# esquema001.net
KiCad netlist of a schematic drawn in EAGLE
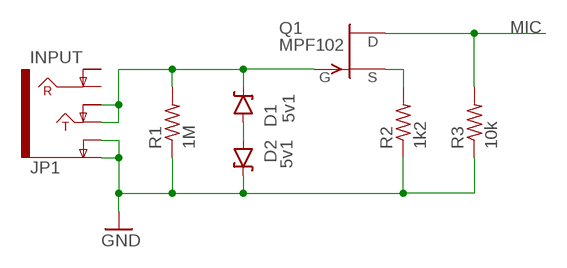
[diagram p0: schematic, sheet 1]
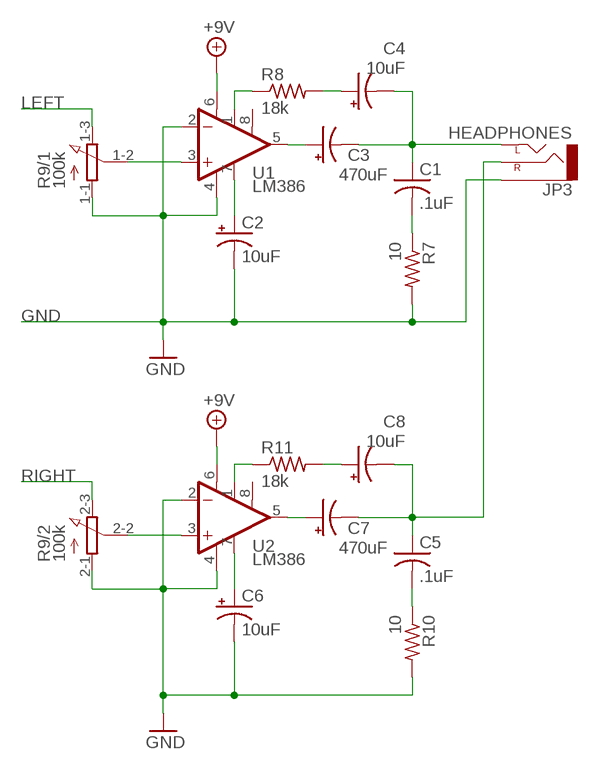
[diagram p1: schematic, sheet 2]
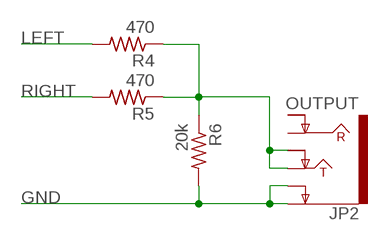
[diagram p2: schematic, sheet 3]
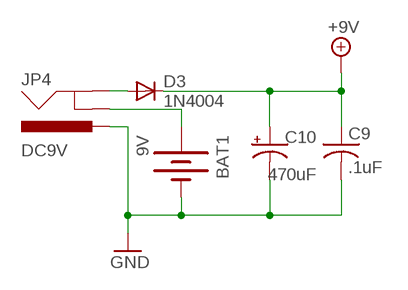
[diagram p3: schematic, sheet 4]

(export (version "E")
  (design (tool "Eeschema 10.0.6"))
  (components
    (comp (ref "BAT1")
      (value "9V")
      (footprint "eagle-import:BATTCON_9V")
      (libsource (lib "eagle-import") (part "BATTERY9V"))
    )
    (comp (ref "C9")
      (value ".1uF")
      (footprint "eagle-import:C050-024X044")
      (libsource (lib "eagle-import") (part "C-US050-024X044"))
    )
    (comp (ref "C10")
      (value "470uF")
      (footprint "eagle-import:E2,5-7")
      (libsource (lib "eagle-import") (part "CPOL-USE2.5-7"))
    )
    (comp (ref "D3")
      (value "1N4004")
      (footprint "eagle-import:DO41-10")
      (libsource (lib "eagle-import") (part "1N4004"))
    )
    (comp (ref "JP4")
      (value "DC9V")
      (footprint "eagle-import:POWER_JACK_PTH")
      (libsource (lib "eagle-import") (part "POWER_JACKPTH"))
    )
    (comp (ref "D1")
      (value "5v1")
      (footprint "eagle-import:DIODE-ZENER")
      (libsource (lib "eagle-import") (part "DIODE-ZENERPTH"))
    )
    (comp (ref "D2")
      (value "5v1")
      (footprint "eagle-import:DIODE-ZENER")
      (libsource (lib "eagle-import") (part "DIODE-ZENERPTH"))
    )
    (comp (ref "JP1")
      (value "INPUT")
      (footprint "eagle-import:AUDIO-JACK-.25-INCH-HORIZ-PTH")
      (libsource (lib "eagle-import") (part "AUDIO-JACK4-.25-HORIZ-TRS"))
    )
    (comp (ref "Q1")
      (value "MPF102")
      (footprint "eagle-import:TO92-")
      (libsource (lib "eagle-import") (part "?5482N4"))
    )
    (comp (ref "R1")
      (value "1M")
      (footprint "eagle-import:0204_7")
      (libsource (lib "eagle-import") (part "R-US_0204/7"))
    )
    (comp (ref "R2")
      (value "1k2")
      (footprint "eagle-import:0204_7")
      (libsource (lib "eagle-import") (part "R-US_0204/7"))
    )
    (comp (ref "R3")
      (value "10k")
      (footprint "eagle-import:0204_7")
      (libsource (lib "eagle-import") (part "R-US_0204/7"))
    )
    (comp (ref "JP2")
      (value "OUTPUT")
      (footprint "eagle-import:AUDIO-JACK-.25-INCH-HORIZ-PTH")
      (libsource (lib "eagle-import") (part "AUDIO-JACK4-.25-HORIZ-TRS"))
    )
    (comp (ref "R4")
      (value "470")
      (footprint "eagle-import:0204_7")
      (libsource (lib "eagle-import") (part "R-US_0204/7"))
    )
    (comp (ref "R5")
      (value "470")
      (footprint "eagle-import:0204_7")
      (libsource (lib "eagle-import") (part "R-US_0204/7"))
    )
    (comp (ref "R6")
      (value "20k")
      (footprint "eagle-import:0204_7")
      (libsource (lib "eagle-import") (part "R-US_0204/7"))
    )
    (comp (ref "C1")
      (value ".1uF")
      (footprint "eagle-import:C050-024X044")
      (libsource (lib "eagle-import") (part "C-US050-024X044"))
    )
    (comp (ref "C2")
      (value "10uF")
      (footprint "eagle-import:E2,5-7")
      (libsource (lib "eagle-import") (part "CPOL-USE2.5-7"))
    )
    (comp (ref "C3")
      (value "470uF")
      (footprint "eagle-import:E2,5-7")
      (libsource (lib "eagle-import") (part "CPOL-USE2.5-7"))
    )
    (comp (ref "C4")
      (value "10uF")
      (footprint "eagle-import:E2,5-7")
      (libsource (lib "eagle-import") (part "CPOL-USE2.5-7"))
    )
    (comp (ref "C5")
      (value ".1uF")
      (footprint "eagle-import:C050-024X044")
      (libsource (lib "eagle-import") (part "C-US050-024X044"))
    )
    (comp (ref "C6")
      (value "10uF")
      (footprint "eagle-import:E2,5-7")
      (libsource (lib "eagle-import") (part "CPOL-USE2.5-7"))
    )
    (comp (ref "C7")
      (value "470uF")
      (footprint "eagle-import:E2,5-7")
      (libsource (lib "eagle-import") (part "CPOL-USE2.5-7"))
    )
    (comp (ref "C8")
      (value "10uF")
      (footprint "eagle-import:E2,5-7")
      (libsource (lib "eagle-import") (part "CPOL-USE2.5-7"))
    )
    (comp (ref "JP3")
      (value "HEADPHONES")
      (footprint "eagle-import:AUDIO-JACK")
      (libsource (lib "eagle-import") (part "AUDIO-JACKPTH"))
    )
    (comp (ref "R7")
      (value "10")
      (footprint "eagle-import:0204_7")
      (libsource (lib "eagle-import") (part "R-US_0204/7"))
    )
    (comp (ref "R8")
      (value "18k")
      (footprint "eagle-import:0204_7")
      (libsource (lib "eagle-import") (part "R-US_0204/7"))
    )
    (comp (ref "R9")
      (value "100k")
      (footprint "eagle-import:3RP_1610G")
      (libsource (lib "eagle-import") (part "3RP/1610G"))
    )
    (comp (ref "R10")
      (value "10")
      (footprint "eagle-import:0204_7")
      (libsource (lib "eagle-import") (part "R-US_0204/7"))
    )
    (comp (ref "R11")
      (value "18k")
      (footprint "eagle-import:0204_7")
      (libsource (lib "eagle-import") (part "R-US_0204/7"))
    )
    (comp (ref "U1")
      (value "LM386")
      (footprint "eagle-import:DIP08")
      (libsource (lib "eagle-import") (part "LM386"))
    )
    (comp (ref "U2")
      (value "LM386")
      (footprint "eagle-import:DIP08")
      (libsource (lib "eagle-import") (part "LM386"))
    )
  )
  (nets
    (net (code "1") (name "+9V") (class "Default")
      (node (ref "C10") (pin "+") (pinfunction "+_+") (pintype "passive"))
      (node (ref "C9") (pin "1") (pinfunction "1_1") (pintype "passive"))
      (node (ref "D3") (pin "C") (pinfunction "C_C") (pintype "passive"))
      (node (ref "U1") (pin "6") (pinfunction "V+_6") (pintype "power_in"))
      (node (ref "U2") (pin "6") (pinfunction "V+_6") (pintype "power_in"))
    )
    (net (code "2") (name "GND") (class "Default")
      (node (ref "BAT1") (pin "-") (pinfunction "-_-") (pintype "power_in"))
      (node (ref "C10") (pin "-") (pinfunction "-_-") (pintype "passive"))
      (node (ref "C2") (pin "-") (pinfunction "-_-") (pintype "passive"))
      (node (ref "C6") (pin "-") (pinfunction "-_-") (pintype "passive"))
      (node (ref "C9") (pin "2") (pinfunction "2_2") (pintype "passive"))
      (node (ref "D2") (pin "P$1") (pinfunction "C_P$1") (pintype "passive"))
      (node (ref "JP1") (pin "SLEEVE") (pinfunction "EARTH_SLEEVE") (pintype "bidirectional"))
      (node (ref "JP1") (pin "SLEEVE-NORM") (pinfunction "EARTH-NORM_SLEEVE-NORM") (pintype "bidirectional"))
      (node (ref "JP2") (pin "SLEEVE") (pinfunction "EARTH_SLEEVE") (pintype "bidirectional"))
      (node (ref "JP2") (pin "SLEEVE-NORM") (pinfunction "EARTH-NORM_SLEEVE-NORM") (pintype "bidirectional"))
      (node (ref "JP3") (pin "SLEEVE") (pinfunction "SLEEVE_SLEEVE") (pintype "bidirectional"))
      (node (ref "JP4") (pin "PWR") (pinfunction "PWR_PWR") (pintype "bidirectional"))
      (node (ref "R1") (pin "1") (pinfunction "1_1") (pintype "passive"))
      (node (ref "R10") (pin "2") (pinfunction "2_2") (pintype "passive"))
      (node (ref "R2") (pin "1") (pinfunction "1_1") (pintype "passive"))
      (node (ref "R3") (pin "1") (pinfunction "1_1") (pintype "passive"))
      (node (ref "R6") (pin "2") (pinfunction "2_2") (pintype "passive"))
      (node (ref "R7") (pin "2") (pinfunction "2_2") (pintype "passive"))
      (node (ref "R9") (pin "1-1") (pinfunction "A_1-1") (pintype "passive"))
      (node (ref "R9") (pin "2-1") (pinfunction "A_2-1") (pintype "passive"))
      (node (ref "U1") (pin "2") (pinfunction "-IN_2") (pintype "input"))
      (node (ref "U1") (pin "4") (pinfunction "V-_4") (pintype "power_in"))
      (node (ref "U2") (pin "2") (pinfunction "-IN_2") (pintype "input"))
      (node (ref "U2") (pin "4") (pinfunction "V-_4") (pintype "power_in"))
    )
    (net (code "3") (name "LEFT") (class "Default")
      (node (ref "R4") (pin "2") (pinfunction "2_2") (pintype "passive"))
      (node (ref "R9") (pin "1-3") (pinfunction "E_1-3") (pintype "passive"))
    )
    (net (code "4") (name "MIC") (class "Default")
      (node (ref "Q1") (pin "3") (pinfunction "D_3") (pintype "passive"))
      (node (ref "R3") (pin "2") (pinfunction "2_2") (pintype "passive"))
    )
    (net (code "5") (name "Net-(BAT1-Pad+)") (class "Default")
      (node (ref "BAT1") (pin "+") (pinfunction "+_+") (pintype "power_in"))
      (node (ref "JP4") (pin "GNDBREAK") (pinfunction "GNDBREAK_GNDBREAK") (pintype "bidirectional"))
    )
    (net (code "6") (name "Net-(C1-Pad2)") (class "Default")
      (node (ref "C1") (pin "2") (pinfunction "2_2") (pintype "passive"))
      (node (ref "R7") (pin "1") (pinfunction "1_1") (pintype "passive"))
    )
    (net (code "7") (name "Net-(C4-Pad+)") (class "Default")
      (node (ref "C4") (pin "+") (pinfunction "+_+") (pintype "passive"))
      (node (ref "R8") (pin "2") (pinfunction "2_2") (pintype "passive"))
    )
    (net (code "8") (name "Net-(C5-Pad2)") (class "Default")
      (node (ref "C5") (pin "2") (pinfunction "2_2") (pintype "passive"))
      (node (ref "R10") (pin "1") (pinfunction "1_1") (pintype "passive"))
    )
    (net (code "9") (name "Net-(C8-Pad+)") (class "Default")
      (node (ref "C8") (pin "+") (pinfunction "+_+") (pintype "passive"))
      (node (ref "R11") (pin "2") (pinfunction "2_2") (pintype "passive"))
    )
    (net (code "10") (name "Net-(D1-A)") (class "Default")
      (node (ref "D1") (pin "P$2") (pinfunction "A_P$2") (pintype "passive"))
      (node (ref "D2") (pin "P$2") (pinfunction "A_P$2") (pintype "passive"))
    )
    (net (code "11") (name "Net-(D1-C)") (class "Default")
      (node (ref "D1") (pin "P$1") (pinfunction "C_P$1") (pintype "passive"))
      (node (ref "JP1") (pin "TIP") (pinfunction "TIP_TIP") (pintype "bidirectional"))
      (node (ref "JP1") (pin "TIP-NORM") (pinfunction "TIP-NORM_TIP-NORM") (pintype "bidirectional"))
      (node (ref "Q1") (pin "1") (pinfunction "G_1") (pintype "passive"))
      (node (ref "R1") (pin "2") (pinfunction "2_2") (pintype "passive"))
    )
    (net (code "12") (name "Net-(D3-PadA)") (class "Default")
      (node (ref "D3") (pin "A") (pinfunction "A_A") (pintype "passive"))
      (node (ref "JP4") (pin "GND") (pinfunction "GND_GND") (pintype "bidirectional"))
    )
    (net (code "13") (name "Net-(JP2-PadTIP)") (class "Default")
      (node (ref "JP2") (pin "TIP") (pinfunction "TIP_TIP") (pintype "bidirectional"))
      (node (ref "JP2") (pin "TIP-NORM") (pinfunction "TIP-NORM_TIP-NORM") (pintype "bidirectional"))
      (node (ref "R4") (pin "1") (pinfunction "1_1") (pintype "passive"))
      (node (ref "R5") (pin "1") (pinfunction "1_1") (pintype "passive"))
      (node (ref "R6") (pin "1") (pinfunction "1_1") (pintype "passive"))
    )
    (net (code "14") (name "Net-(JP3-LEFT)") (class "Default")
      (node (ref "C1") (pin "1") (pinfunction "1_1") (pintype "passive"))
      (node (ref "C3") (pin "-") (pinfunction "-_-") (pintype "passive"))
      (node (ref "C4") (pin "-") (pinfunction "-_-") (pintype "passive"))
      (node (ref "JP3") (pin "TIP") (pinfunction "LEFT_TIP") (pintype "bidirectional"))
    )
    (net (code "15") (name "Net-(JP3-RIGHT)") (class "Default")
      (node (ref "C5") (pin "1") (pinfunction "1_1") (pintype "passive"))
      (node (ref "C7") (pin "-") (pinfunction "-_-") (pintype "passive"))
      (node (ref "C8") (pin "-") (pinfunction "-_-") (pintype "passive"))
      (node (ref "JP3") (pin "RING") (pinfunction "RIGHT_RING") (pintype "bidirectional"))
    )
    (net (code "16") (name "Net-(Q1-S)") (class "Default")
      (node (ref "Q1") (pin "2") (pinfunction "S_2") (pintype "passive"))
      (node (ref "R2") (pin "2") (pinfunction "2_2") (pintype "passive"))
    )
    (net (code "17") (name "Net-(R8-Pad1)") (class "Default")
      (node (ref "R8") (pin "1") (pinfunction "1_1") (pintype "passive"))
      (node (ref "U1") (pin "1") (pinfunction "GAIN_1") (pintype "bidirectional"))
    )
    (net (code "18") (name "Net-(R9A-S)") (class "Default")
      (node (ref "R9") (pin "1-2") (pinfunction "S_1-2") (pintype "passive"))
      (node (ref "U1") (pin "3") (pinfunction "+IN_3") (pintype "input"))
    )
    (net (code "19") (name "Net-(R9B-S)") (class "Default")
      (node (ref "R9") (pin "2-2") (pinfunction "S_2-2") (pintype "passive"))
      (node (ref "U2") (pin "3") (pinfunction "+IN_3") (pintype "input"))
    )
    (net (code "20") (name "Net-(R11-Pad1)") (class "Default")
      (node (ref "R11") (pin "1") (pinfunction "1_1") (pintype "passive"))
      (node (ref "U2") (pin "1") (pinfunction "GAIN_1") (pintype "bidirectional"))
    )
    (net (code "21") (name "Net-(U1-BP)") (class "Default")
      (node (ref "C2") (pin "+") (pinfunction "+_+") (pintype "passive"))
      (node (ref "U1") (pin "7") (pinfunction "BP_7") (pintype "bidirectional"))
    )
    (net (code "22") (name "Net-(U1-OUT)") (class "Default")
      (node (ref "C3") (pin "+") (pinfunction "+_+") (pintype "passive"))
      (node (ref "U1") (pin "5") (pinfunction "OUT_5") (pintype "output"))
    )
    (net (code "23") (name "Net-(U2-BP)") (class "Default")
      (node (ref "C6") (pin "+") (pinfunction "+_+") (pintype "passive"))
      (node (ref "U2") (pin "7") (pinfunction "BP_7") (pintype "bidirectional"))
    )
    (net (code "24") (name "Net-(U2-OUT)") (class "Default")
      (node (ref "C7") (pin "+") (pinfunction "+_+") (pintype "passive"))
      (node (ref "U2") (pin "5") (pinfunction "OUT_5") (pintype "output"))
    )
    (net (code "25") (name "RIGHT") (class "Default")
      (node (ref "R5") (pin "2") (pinfunction "2_2") (pintype "passive"))
      (node (ref "R9") (pin "2-3") (pinfunction "E_2-3") (pintype "passive"))
    )
    (net (code "26") (name "unconnected-(JP1-PadRING)") (class "Default")
      (node (ref "JP1") (pin "RING") (pinfunction "RING_RING") (pintype "bidirectional"))
    )
    (net (code "27") (name "unconnected-(JP1-PadRING-NORM)") (class "Default")
      (node (ref "JP1") (pin "RING-NORM") (pinfunction "RING-NORM_RING-NORM") (pintype "bidirectional"))
    )
    (net (code "28") (name "unconnected-(JP2-PadRING)") (class "Default")
      (node (ref "JP2") (pin "RING") (pinfunction "RING_RING") (pintype "bidirectional"))
    )
    (net (code "29") (name "unconnected-(JP2-PadRING-NORM)") (class "Default")
      (node (ref "JP2") (pin "RING-NORM") (pinfunction "RING-NORM_RING-NORM") (pintype "bidirectional"))
    )
    (net (code "30") (name "unconnected-(U1-GAIN-Pad8)") (class "Default")
      (node (ref "U1") (pin "8") (pinfunction "GAIN_8") (pintype "bidirectional"))
    )
    (net (code "31") (name "unconnected-(U2-GAIN-Pad8)") (class "Default")
      (node (ref "U2") (pin "8") (pinfunction "GAIN_8") (pintype "bidirectional"))
    )
  )
)
